# Sheet1_NQI_MEZ.net
KiCad netlist of a schematic drawn in Altium Designer
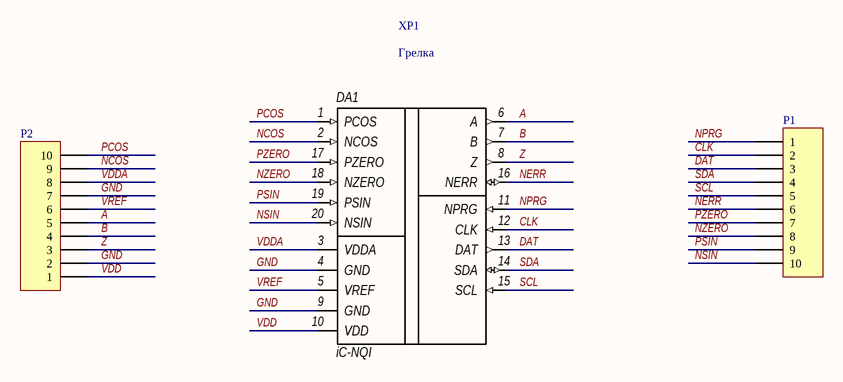
[diagram p0: Sheet1_NQI_MEZ.SchDoc]

(export (version "E")
  (design (tool "Eeschema 10.0.6"))
  (components
    (comp (ref "DA1")
      (value "iC-NQI")
      (footprint "iC-NQI")
      (description "Оптический энкодер")
      (libsource (lib "VPL") (part "iC-NQI"))
    )
    (comp (ref "P1")
      (value "Header 10")
      (footprint "HDR1X10")
      (description "Header, 10-Pin")
      (fields (field (name "PUBLISHER") "Altium Limited"))
      (libsource (lib "") (part "Header 10_1"))
    )
    (comp (ref "P2")
      (value "Header 10")
      (footprint "HDR1X10")
      (description "Header, 10-Pin")
      (fields (field (name "PUBLISHER") "Altium Limited"))
      (libsource (lib "Miscellaneous Connectors") (part "Header 10"))
    )
    (comp (ref "XP1") (value "Грелка") (footprint "Грелка") (libsource (lib "VPL") (part "Грелка")))
  )
  (nets
    (net (code "1") (name "/A") (class "Default")
      (node (ref "DA1") (pin "6") (pinfunction "A_6") (pintype "output"))
      (node (ref "P2") (pin "5") (pinfunction "5_5") (pintype "passive"))
    )
    (net (code "2") (name "/B") (class "Default")
      (node (ref "DA1") (pin "7") (pinfunction "B_7") (pintype "output"))
      (node (ref "P2") (pin "4") (pinfunction "4_4") (pintype "passive"))
    )
    (net (code "3") (name "/CLK") (class "Default")
      (node (ref "DA1") (pin "12") (pinfunction "CLK_12") (pintype "input"))
      (node (ref "P1") (pin "2") (pinfunction "2_2") (pintype "passive"))
    )
    (net (code "4") (name "/DAT") (class "Default")
      (node (ref "DA1") (pin "13") (pinfunction "DAT_13") (pintype "output"))
      (node (ref "P1") (pin "3") (pinfunction "3_3") (pintype "passive"))
    )
    (net (code "5") (name "/GND") (class "Default")
      (node (ref "DA1") (pin "4") (pinfunction "GND_4") (pintype "power_in"))
      (node (ref "DA1") (pin "9") (pinfunction "GND_9") (pintype "power_in"))
      (node (ref "P2") (pin "2") (pinfunction "2_2") (pintype "passive"))
      (node (ref "P2") (pin "7") (pinfunction "7_7") (pintype "passive"))
    )
    (net (code "6") (name "/NCOS") (class "Default")
      (node (ref "DA1") (pin "2") (pinfunction "NCOS_2") (pintype "input"))
      (node (ref "P2") (pin "9") (pinfunction "9_9") (pintype "passive"))
    )
    (net (code "7") (name "/NERR") (class "Default")
      (node (ref "DA1") (pin "16") (pinfunction "NERR_16") (pintype "bidirectional"))
      (node (ref "P1") (pin "6") (pinfunction "6_6") (pintype "passive"))
    )
    (net (code "8") (name "/NPRG") (class "Default")
      (node (ref "DA1") (pin "11") (pinfunction "NPRG_11") (pintype "input"))
      (node (ref "P1") (pin "1") (pinfunction "1_1") (pintype "passive"))
    )
    (net (code "9") (name "/NSIN") (class "Default")
      (node (ref "DA1") (pin "20") (pinfunction "NSIN_20") (pintype "input"))
      (node (ref "P1") (pin "10") (pinfunction "10_10") (pintype "passive"))
    )
    (net (code "10") (name "/NZERO") (class "Default")
      (node (ref "DA1") (pin "18") (pinfunction "NZERO_18") (pintype "input"))
      (node (ref "P1") (pin "8") (pinfunction "8_8") (pintype "passive"))
    )
    (net (code "11") (name "/PCOS") (class "Default")
      (node (ref "DA1") (pin "1") (pinfunction "PCOS_1") (pintype "input"))
      (node (ref "P2") (pin "10") (pinfunction "10_10") (pintype "passive"))
    )
    (net (code "12") (name "/PSIN") (class "Default")
      (node (ref "DA1") (pin "19") (pinfunction "PSIN_19") (pintype "input"))
      (node (ref "P1") (pin "9") (pinfunction "9_9") (pintype "passive"))
    )
    (net (code "13") (name "/PZERO") (class "Default")
      (node (ref "DA1") (pin "17") (pinfunction "PZERO_17") (pintype "input"))
      (node (ref "P1") (pin "7") (pinfunction "7_7") (pintype "passive"))
    )
    (net (code "14") (name "/SCL") (class "Default")
      (node (ref "DA1") (pin "15") (pinfunction "SCL_15") (pintype "input"))
      (node (ref "P1") (pin "5") (pinfunction "5_5") (pintype "passive"))
    )
    (net (code "15") (name "/SDA") (class "Default")
      (node (ref "DA1") (pin "14") (pinfunction "SDA_14") (pintype "bidirectional"))
      (node (ref "P1") (pin "4") (pinfunction "4_4") (pintype "passive"))
    )
    (net (code "16") (name "/VDD") (class "Default")
      (node (ref "DA1") (pin "10") (pinfunction "VDD_10") (pintype "power_in"))
      (node (ref "P2") (pin "1") (pinfunction "1_1") (pintype "passive"))
    )
    (net (code "17") (name "/VDDA") (class "Default")
      (node (ref "DA1") (pin "3") (pinfunction "VDDA_3") (pintype "power_in"))
      (node (ref "P2") (pin "8") (pinfunction "8_8") (pintype "passive"))
    )
    (net (code "18") (name "/VREF") (class "Default")
      (node (ref "DA1") (pin "5") (pinfunction "VREF_5") (pintype "power_in"))
      (node (ref "P2") (pin "6") (pinfunction "6_6") (pintype "passive"))
    )
    (net (code "19") (name "/Z") (class "Default")
      (node (ref "DA1") (pin "8") (pinfunction "Z_8") (pintype "output"))
      (node (ref "P2") (pin "3") (pinfunction "3_3") (pintype "passive"))
    )
  )
)
